# PowerRegulator.net
KiCad netlist of a schematic drawn in Altium Designer
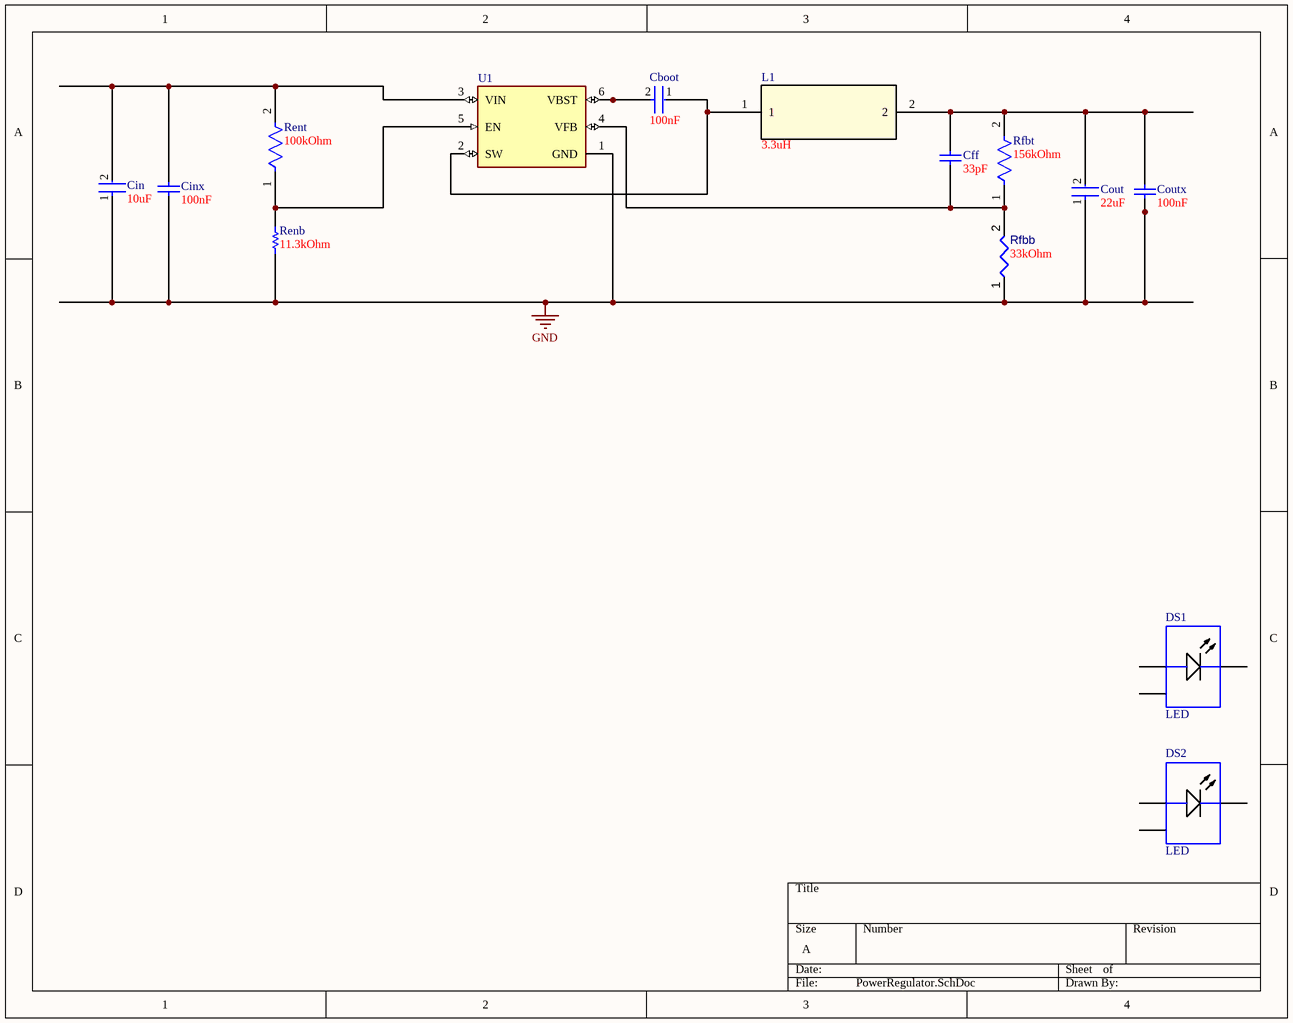
[diagram p0: PowerRegulator.SchDoc]

(export (version "E")
  (design (tool "Eeschema 10.0.6"))
  (components
    (comp (ref "Cboot")
      (value "100nF")
      (footprint "FP-GRM15-MFG")
      (description "CAP CER 0.1UF 16V X7R 0402")
      (fields (field (name "MANUFACTURER PART NUMBER") "GRM155R71C104KA88D") (field (name "TOLERANCE") "10%"))
      (libsource (lib "Altium Content Vault") (part "236180d848d6139a670b325ea6854c9"))
    )
    (comp (ref "Cff")
      (value "33pF")
      (footprint "CAPC1005X55X25ML05T10")
      (fields (field (name "MANUFACTURER") "Murata") (field (name "PART NUMBER") "GRM1555C1E330JA01D"))
      (libsource (lib "Altium Content Vault") (part "CAP"))
    )
    (comp (ref "Cin")
      (value "10uF")
      (footprint "FP-GRM21B-0_15-IPC_A")
      (description "Chip Multilayer Ceramic Capacitors for General Purpose, 0805, 10uF, X5R, 15%, 20%, 25V")
      (fields (field (name "TOLERANCE") "20%"))
      (libsource (lib "Altium Content Vault") (part "b4654b650e69147ec39a6b967a45e02"))
    )
    (comp (ref "Cinx")
      (value "100nF")
      (footprint "CAPC1608X90X35ML10T15")
      (description "Chip Capacitor, 0.1 uF, +/- 10%, 50 V, -55 to 125 degC, 0603 (1608 Metric), RoHS, Tape and Reel")
      (fields (field (name "TOLERANCE") "10%") (field (name "VOLTAGE") "50V"))
      (libsource (lib "Altium Content Vault") (part "CAP-NP-2"))
    )
    (comp (ref "Cout")
      (value "22uF")
      (footprint "FP-GRM21B-0_2-e0_2_0_7-IPC_C")
      (description "Chip Multilayer Ceramic Capacitors for General Purpose, 0805, 22uF, X5R, 15%, 20%, 10V")
      (fields (field (name "TOLERANCE") "20%") (field (name "VOLTAGE") "10V"))
      (libsource (lib "Altium Content Vault") (part "b4654b650e69147ec39a6b967a45e02"))
    )
    (comp (ref "Coutx")
      (value "100nF")
      (footprint "CAPC1608X90X35LL10T15")
      (fields (field (name "PART NUMBER") "GRM188R71E104KA01D") (field (name "MANUFACTURER") "Murata"))
      (libsource (lib "Altium Content Vault") (part "CAP"))
    )
    (comp (ref "DS1")
      (value "LED")
      (footprint "CREE-MK-R-2_V")
      (description "LED, White, 12 V, 2-Pin SMD, RoHS, Tape and Reel")
      (libsource (lib "Altium Content Vault") (part "LED_WHITE-3"))
    )
    (comp (ref "DS2")
      (value "LED")
      (footprint "CREE-MK-R-2_V")
      (description "LED, White, 12 V, 2-Pin SMD, RoHS, Tape and Reel")
      (libsource (lib "Altium Content Vault") (part "LED_WHITE-3"))
    )
    (comp (ref "L1")
      (value "3.3uH")
      (footprint "NPI54C3R3MTRF_NIC")
      (description "No Description Available")
      (fields
        (field (name "MANUFACTURER_PART_NUMBER") "NPI54C3R3MTRF")
        (field (name "COPYRIGHT") "Copyright (C) 2024 Ultra Librarian. All rights reserved.")
      )
      (libsource (lib "Altium Space") (part "NPI54C3R3MTRF"))
    )
    (comp (ref "Renb")
      (value "11.3kOhm")
      (footprint "RESC1005X40X25ML05T05")
      (fields (field (name "PART NUMBER") "CRCW040211K3FKED") (field (name "MANUFACTURER") "Vishay Dale"))
      (libsource (lib "Altium Content Vault") (part "RES"))
    )
    (comp (ref "Rent")
      (value "100kOhm")
      (footprint "FP-CRCW0402-e3-IPC_C")
      (description "RES Thick Film, 100kΩ, 1%, 0.063W, 100ppm/°C, 0402")
      (fields (field (name "TOLERANCE") "1%"))
      (libsource (lib "Altium Content Vault") (part "1029c3af85768c4190bb7ad29bc67b5"))
    )
    (comp (ref "Rfbb")
      (value "33kOhm")
      (footprint "RESC1005X40X25ML10T10")
      (description "Chip Resistor, 33 KOhm, +/- 5%, 0.063 W, -55 to 155 degC, 0402 (1005 Metric)")
      (fields (field (name "TOLERANCE") "5%") (field (name "POWER") "63mW"))
      (libsource (lib "Altium Space") (part "RES-2"))
    )
    (comp (ref "Rfbt")
      (value "156kOhm")
      (footprint "FP-CRCW0402-e3-IPC_C")
      (description "RES Thick Film, 158kΩ, 1%, 0.063W, 100ppm/°C, 0402")
      (fields (field (name "TOLERANCE") "1%"))
      (libsource (lib "Altium Content Vault") (part "1029c3af85768c4190bb7ad29bc67b5"))
    )
    (comp (ref "U1")
      (value "TPS562201DDCR")
      (footprint "FP-DDC0006A-IPC_C")
      (description "IC REG BUCK ADJ 2A TSOT23-6")
      (libsource (lib "Altium Content Vault") (part "957e164956730ea4bf6293280af19fc"))
    )
  )
  (nets
    (net (code "1") (name "GND") (class "Default")
      (node (ref "Cin") (pin "1") (pinfunction "1_1") (pintype "passive"))
      (node (ref "Cinx") (pin "1") (pinfunction "1_1") (pintype "passive"))
      (node (ref "Cout") (pin "1") (pinfunction "1_1") (pintype "passive"))
      (node (ref "Coutx") (pin "1") (pinfunction "1_1") (pintype "passive"))
      (node (ref "Renb") (pin "1") (pinfunction "1_1") (pintype "passive"))
      (node (ref "Rfbb") (pin "1") (pinfunction "1_1") (pintype "passive"))
      (node (ref "U1") (pin "1") (pinfunction "GND_1") (pintype "power_in"))
    )
    (net (code "2") (name "Net-(Cff-Pad2)") (class "Default")
      (node (ref "Cff") (pin "2") (pinfunction "2_2") (pintype "passive"))
      (node (ref "Cout") (pin "2") (pinfunction "2_2") (pintype "passive"))
      (node (ref "Coutx") (pin "2") (pinfunction "2_2") (pintype "passive"))
      (node (ref "L1") (pin "2") (pinfunction "2_2") (pintype "passive"))
      (node (ref "Rfbt") (pin "2") (pinfunction "2_2") (pintype "passive"))
    )
    (net (code "3") (name "Net-(U1-EN)") (class "Default")
      (node (ref "Renb") (pin "2") (pinfunction "2_2") (pintype "passive"))
      (node (ref "Rent") (pin "1") (pinfunction "1_1") (pintype "passive"))
      (node (ref "U1") (pin "5") (pinfunction "EN_5") (pintype "input"))
    )
    (net (code "4") (name "Net-(U1-SW)") (class "Default")
      (node (ref "Cboot") (pin "1") (pinfunction "1_1") (pintype "passive"))
      (node (ref "L1") (pin "1") (pinfunction "1_1") (pintype "passive"))
      (node (ref "U1") (pin "2") (pinfunction "SW_2") (pintype "bidirectional"))
    )
    (net (code "5") (name "Net-(U1-VBST)") (class "Default")
      (node (ref "Cboot") (pin "2") (pinfunction "2_2") (pintype "passive"))
      (node (ref "U1") (pin "6") (pinfunction "VBST_6") (pintype "bidirectional"))
    )
    (net (code "6") (name "Net-(U1-VFB)") (class "Default")
      (node (ref "Cff") (pin "1") (pinfunction "1_1") (pintype "passive"))
      (node (ref "Rfbb") (pin "2") (pinfunction "2_2") (pintype "passive"))
      (node (ref "Rfbt") (pin "1") (pinfunction "1_1") (pintype "passive"))
      (node (ref "U1") (pin "4") (pinfunction "VFB_4") (pintype "bidirectional"))
    )
    (net (code "7") (name "Net-(U1-VIN)") (class "Default")
      (node (ref "Cin") (pin "2") (pinfunction "2_2") (pintype "passive"))
      (node (ref "Cinx") (pin "2") (pinfunction "2_2") (pintype "passive"))
      (node (ref "Rent") (pin "2") (pinfunction "2_2") (pintype "passive"))
      (node (ref "U1") (pin "3") (pinfunction "VIN_3") (pintype "bidirectional"))
    )
    (net (code "8") (name "unconnected-(DS1-A-Pad1)") (class "Default")
      (node (ref "DS1") (pin "1") (pinfunction "A_1") (pintype "passive"))
    )
    (net (code "9") (name "unconnected-(DS1-EP-Pad3)") (class "Default")
      (node (ref "DS1") (pin "3") (pinfunction "EP_3") (pintype "passive"))
    )
    (net (code "10") (name "unconnected-(DS1-K-Pad2)") (class "Default")
      (node (ref "DS1") (pin "2") (pinfunction "K_2") (pintype "passive"))
    )
    (net (code "11") (name "unconnected-(DS2-A-Pad1)") (class "Default")
      (node (ref "DS2") (pin "1") (pinfunction "A_1") (pintype "passive"))
    )
    (net (code "12") (name "unconnected-(DS2-EP-Pad3)") (class "Default")
      (node (ref "DS2") (pin "3") (pinfunction "EP_3") (pintype "passive"))
    )
    (net (code "13") (name "unconnected-(DS2-K-Pad2)") (class "Default")
      (node (ref "DS2") (pin "2") (pinfunction "K_2") (pintype "passive"))
    )
  )
)
